# LEDcontroller.net
KiCad netlist of a schematic drawn in Altium Designer
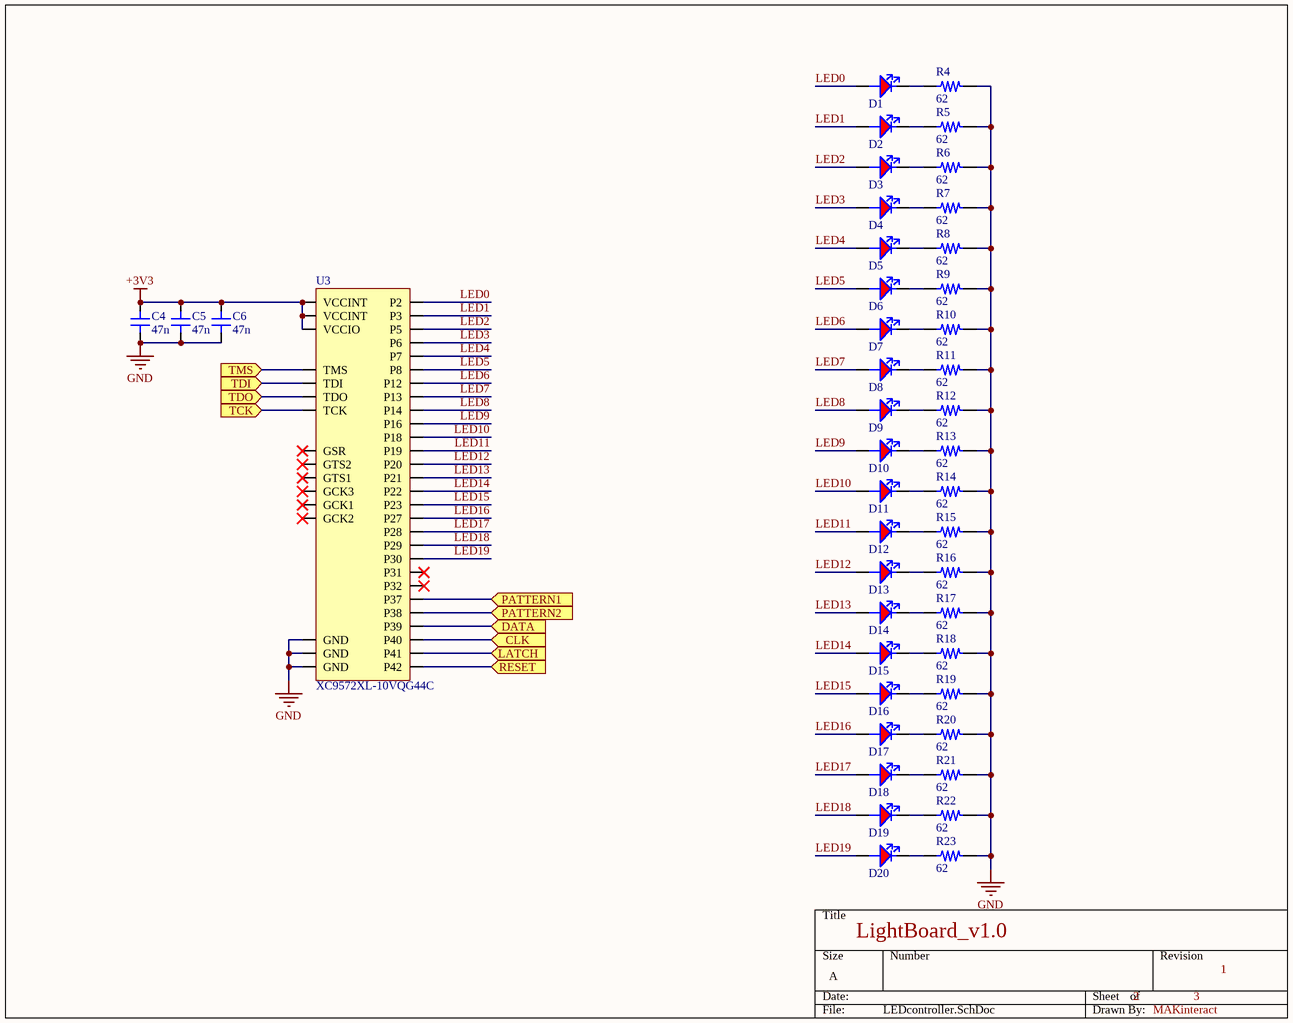
[diagram p0: LEDcontroller.SchDoc]

(export (version "E")
  (design (tool "Eeschema 10.0.6"))
  (components
    (comp (ref "C4")
      (value "47n")
      (description "Cap Ceramic 0.047uF 50V X7R 5% SMD 0805 125C Paper T/R")
      (fields
        (field (name "MANUFACTURER") "Yageo")
        (field (name "MANUFACTURER PART NUMBER") "CC0805JRX7R9BB473")
      )
      (libsource (lib "LightBoard_v1.0") (part "C0805_47n"))
    )
    (comp (ref "C5")
      (value "47n")
      (description "Cap Ceramic 0.047uF 50V X7R 5% SMD 0805 125C Paper T/R")
      (fields
        (field (name "MANUFACTURER") "Yageo")
        (field (name "MANUFACTURER PART NUMBER") "CC0805JRX7R9BB473")
      )
      (libsource (lib "LightBoard_v1.0") (part "C0805_47n"))
    )
    (comp (ref "C6")
      (value "47n")
      (description "Cap Ceramic 0.047uF 50V X7R 5% SMD 0805 125C Paper T/R")
      (fields
        (field (name "MANUFACTURER") "Yageo")
        (field (name "MANUFACTURER PART NUMBER") "CC0805JRX7R9BB473")
      )
      (libsource (lib "LightBoard_v1.0") (part "C0805_47n"))
    )
    (comp (ref "D1")
      (value "LED0402_RED")
      (description "Led red")
      (fields
        (field (name "MANUFACTURER") "Everlight")
        (field (name "MANUFACTURER PART NUMBER") "EAST1005BA0")
      )
      (libsource (lib "LightBoard_v1.0") (part "LED0402_RED"))
    )
    (comp (ref "D2")
      (value "LED0402_RED")
      (description "Led red")
      (fields
        (field (name "MANUFACTURER") "Everlight")
        (field (name "MANUFACTURER PART NUMBER") "EAST1005BA0")
      )
      (libsource (lib "LightBoard_v1.0") (part "LED0402_RED"))
    )
    (comp (ref "D3")
      (value "LED0402_RED")
      (description "Led red")
      (fields
        (field (name "MANUFACTURER") "Everlight")
        (field (name "MANUFACTURER PART NUMBER") "EAST1005BA0")
      )
      (libsource (lib "LightBoard_v1.0") (part "LED0402_RED"))
    )
    (comp (ref "D4")
      (value "LED0402_RED")
      (description "Led red")
      (fields
        (field (name "MANUFACTURER") "Everlight")
        (field (name "MANUFACTURER PART NUMBER") "EAST1005BA0")
      )
      (libsource (lib "LightBoard_v1.0") (part "LED0402_RED"))
    )
    (comp (ref "D5")
      (value "LED0402_RED")
      (description "Led red")
      (fields
        (field (name "MANUFACTURER") "Everlight")
        (field (name "MANUFACTURER PART NUMBER") "EAST1005BA0")
      )
      (libsource (lib "LightBoard_v1.0") (part "LED0402_RED"))
    )
    (comp (ref "D6")
      (value "LED0402_RED")
      (description "Led red")
      (fields
        (field (name "MANUFACTURER") "Everlight")
        (field (name "MANUFACTURER PART NUMBER") "EAST1005BA0")
      )
      (libsource (lib "LightBoard_v1.0") (part "LED0402_RED"))
    )
    (comp (ref "D7")
      (value "LED0402_RED")
      (description "Led red")
      (fields
        (field (name "MANUFACTURER") "Everlight")
        (field (name "MANUFACTURER PART NUMBER") "EAST1005BA0")
      )
      (libsource (lib "LightBoard_v1.0") (part "LED0402_RED"))
    )
    (comp (ref "D8")
      (value "LED0402_RED")
      (description "Led red")
      (fields
        (field (name "MANUFACTURER") "Everlight")
        (field (name "MANUFACTURER PART NUMBER") "EAST1005BA0")
      )
      (libsource (lib "LightBoard_v1.0") (part "LED0402_RED"))
    )
    (comp (ref "D9")
      (value "LED0402_RED")
      (description "Led red")
      (fields
        (field (name "MANUFACTURER") "Everlight")
        (field (name "MANUFACTURER PART NUMBER") "EAST1005BA0")
      )
      (libsource (lib "LightBoard_v1.0") (part "LED0402_RED"))
    )
    (comp (ref "D10")
      (value "LED0402_RED")
      (description "Led red")
      (fields
        (field (name "MANUFACTURER") "Everlight")
        (field (name "MANUFACTURER PART NUMBER") "EAST1005BA0")
      )
      (libsource (lib "LightBoard_v1.0") (part "LED0402_RED"))
    )
    (comp (ref "D11")
      (value "LED0402_RED")
      (description "Led red")
      (fields
        (field (name "MANUFACTURER") "Everlight")
        (field (name "MANUFACTURER PART NUMBER") "EAST1005BA0")
      )
      (libsource (lib "LightBoard_v1.0") (part "LED0402_RED"))
    )
    (comp (ref "D12")
      (value "LED0402_RED")
      (description "Led red")
      (fields
        (field (name "MANUFACTURER") "Everlight")
        (field (name "MANUFACTURER PART NUMBER") "EAST1005BA0")
      )
      (libsource (lib "LightBoard_v1.0") (part "LED0402_RED"))
    )
    (comp (ref "D13")
      (value "LED0402_RED")
      (description "Led red")
      (fields
        (field (name "MANUFACTURER") "Everlight")
        (field (name "MANUFACTURER PART NUMBER") "EAST1005BA0")
      )
      (libsource (lib "LightBoard_v1.0") (part "LED0402_RED"))
    )
    (comp (ref "D14")
      (value "LED0402_RED")
      (description "Led red")
      (fields
        (field (name "MANUFACTURER") "Everlight")
        (field (name "MANUFACTURER PART NUMBER") "EAST1005BA0")
      )
      (libsource (lib "LightBoard_v1.0") (part "LED0402_RED"))
    )
    (comp (ref "D15")
      (value "LED0402_RED")
      (description "Led red")
      (fields
        (field (name "MANUFACTURER") "Everlight")
        (field (name "MANUFACTURER PART NUMBER") "EAST1005BA0")
      )
      (libsource (lib "LightBoard_v1.0") (part "LED0402_RED"))
    )
    (comp (ref "D16")
      (value "LED0402_RED")
      (description "Led red")
      (fields
        (field (name "MANUFACTURER") "Everlight")
        (field (name "MANUFACTURER PART NUMBER") "EAST1005BA0")
      )
      (libsource (lib "LightBoard_v1.0") (part "LED0402_RED"))
    )
    (comp (ref "D17")
      (value "LED0402_RED")
      (description "Led red")
      (fields
        (field (name "MANUFACTURER") "Everlight")
        (field (name "MANUFACTURER PART NUMBER") "EAST1005BA0")
      )
      (libsource (lib "LightBoard_v1.0") (part "LED0402_RED"))
    )
    (comp (ref "D18")
      (value "LED0402_RED")
      (description "Led red")
      (fields
        (field (name "MANUFACTURER") "Everlight")
        (field (name "MANUFACTURER PART NUMBER") "EAST1005BA0")
      )
      (libsource (lib "LightBoard_v1.0") (part "LED0402_RED"))
    )
    (comp (ref "D19")
      (value "LED0402_RED")
      (description "Led red")
      (fields
        (field (name "MANUFACTURER") "Everlight")
        (field (name "MANUFACTURER PART NUMBER") "EAST1005BA0")
      )
      (libsource (lib "LightBoard_v1.0") (part "LED0402_RED"))
    )
    (comp (ref "D20")
      (value "LED0402_RED")
      (description "Led red")
      (fields
        (field (name "MANUFACTURER") "Everlight")
        (field (name "MANUFACTURER PART NUMBER") "EAST1005BA0")
      )
      (libsource (lib "LightBoard_v1.0") (part "LED0402_RED"))
    )
    (comp (ref "R4")
      (value "62")
      (description "RES SMD 62 OHM 1% 1/16W 0402")
      (fields
        (field (name "MANUFACTURER") "Yageo")
        (field (name "MANUFACTURER PART NUMBER") "RC0402FR-0762RL")
      )
      (libsource (lib "LightBoard_v1.0") (part "R0402_62"))
    )
    (comp (ref "R5")
      (value "62")
      (description "RES SMD 62 OHM 1% 1/16W 0402")
      (fields
        (field (name "MANUFACTURER") "Yageo")
        (field (name "MANUFACTURER PART NUMBER") "RC0402FR-0762RL")
      )
      (libsource (lib "LightBoard_v1.0") (part "R0402_62"))
    )
    (comp (ref "R6")
      (value "62")
      (description "RES SMD 62 OHM 1% 1/16W 0402")
      (fields
        (field (name "MANUFACTURER") "Yageo")
        (field (name "MANUFACTURER PART NUMBER") "RC0402FR-0762RL")
      )
      (libsource (lib "LightBoard_v1.0") (part "R0402_62"))
    )
    (comp (ref "R7")
      (value "62")
      (description "RES SMD 62 OHM 1% 1/16W 0402")
      (fields
        (field (name "MANUFACTURER") "Yageo")
        (field (name "MANUFACTURER PART NUMBER") "RC0402FR-0762RL")
      )
      (libsource (lib "LightBoard_v1.0") (part "R0402_62"))
    )
    (comp (ref "R8")
      (value "62")
      (description "RES SMD 62 OHM 1% 1/16W 0402")
      (fields
        (field (name "MANUFACTURER") "Yageo")
        (field (name "MANUFACTURER PART NUMBER") "RC0402FR-0762RL")
      )
      (libsource (lib "LightBoard_v1.0") (part "R0402_62"))
    )
    (comp (ref "R9")
      (value "62")
      (description "RES SMD 62 OHM 1% 1/16W 0402")
      (fields
        (field (name "MANUFACTURER") "Yageo")
        (field (name "MANUFACTURER PART NUMBER") "RC0402FR-0762RL")
      )
      (libsource (lib "LightBoard_v1.0") (part "R0402_62"))
    )
    (comp (ref "R10")
      (value "62")
      (description "RES SMD 62 OHM 1% 1/16W 0402")
      (fields
        (field (name "MANUFACTURER") "Yageo")
        (field (name "MANUFACTURER PART NUMBER") "RC0402FR-0762RL")
      )
      (libsource (lib "LightBoard_v1.0") (part "R0402_62"))
    )
    (comp (ref "R11")
      (value "62")
      (description "RES SMD 62 OHM 1% 1/16W 0402")
      (fields
        (field (name "MANUFACTURER") "Yageo")
        (field (name "MANUFACTURER PART NUMBER") "RC0402FR-0762RL")
      )
      (libsource (lib "LightBoard_v1.0") (part "R0402_62"))
    )
    (comp (ref "R12")
      (value "62")
      (description "RES SMD 62 OHM 1% 1/16W 0402")
      (fields
        (field (name "MANUFACTURER") "Yageo")
        (field (name "MANUFACTURER PART NUMBER") "RC0402FR-0762RL")
      )
      (libsource (lib "LightBoard_v1.0") (part "R0402_62"))
    )
    (comp (ref "R13")
      (value "62")
      (description "RES SMD 62 OHM 1% 1/16W 0402")
      (fields
        (field (name "MANUFACTURER") "Yageo")
        (field (name "MANUFACTURER PART NUMBER") "RC0402FR-0762RL")
      )
      (libsource (lib "LightBoard_v1.0") (part "R0402_62"))
    )
    (comp (ref "R14")
      (value "62")
      (description "RES SMD 62 OHM 1% 1/16W 0402")
      (fields
        (field (name "MANUFACTURER") "Yageo")
        (field (name "MANUFACTURER PART NUMBER") "RC0402FR-0762RL")
      )
      (libsource (lib "LightBoard_v1.0") (part "R0402_62"))
    )
    (comp (ref "R15")
      (value "62")
      (description "RES SMD 62 OHM 1% 1/16W 0402")
      (fields
        (field (name "MANUFACTURER") "Yageo")
        (field (name "MANUFACTURER PART NUMBER") "RC0402FR-0762RL")
      )
      (libsource (lib "LightBoard_v1.0") (part "R0402_62"))
    )
    (comp (ref "R16")
      (value "62")
      (description "RES SMD 62 OHM 1% 1/16W 0402")
      (fields
        (field (name "MANUFACTURER") "Yageo")
        (field (name "MANUFACTURER PART NUMBER") "RC0402FR-0762RL")
      )
      (libsource (lib "LightBoard_v1.0") (part "R0402_62"))
    )
    (comp (ref "R17")
      (value "62")
      (description "RES SMD 62 OHM 1% 1/16W 0402")
      (fields
        (field (name "MANUFACTURER") "Yageo")
        (field (name "MANUFACTURER PART NUMBER") "RC0402FR-0762RL")
      )
      (libsource (lib "LightBoard_v1.0") (part "R0402_62"))
    )
    (comp (ref "R18")
      (value "62")
      (description "RES SMD 62 OHM 1% 1/16W 0402")
      (fields
        (field (name "MANUFACTURER") "Yageo")
        (field (name "MANUFACTURER PART NUMBER") "RC0402FR-0762RL")
      )
      (libsource (lib "LightBoard_v1.0") (part "R0402_62"))
    )
    (comp (ref "R19")
      (value "62")
      (description "RES SMD 62 OHM 1% 1/16W 0402")
      (fields
        (field (name "MANUFACTURER") "Yageo")
        (field (name "MANUFACTURER PART NUMBER") "RC0402FR-0762RL")
      )
      (libsource (lib "LightBoard_v1.0") (part "R0402_62"))
    )
    (comp (ref "R20")
      (value "62")
      (description "RES SMD 62 OHM 1% 1/16W 0402")
      (fields
        (field (name "MANUFACTURER") "Yageo")
        (field (name "MANUFACTURER PART NUMBER") "RC0402FR-0762RL")
      )
      (libsource (lib "LightBoard_v1.0") (part "R0402_62"))
    )
    (comp (ref "R21")
      (value "62")
      (description "RES SMD 62 OHM 1% 1/16W 0402")
      (fields
        (field (name "MANUFACTURER") "Yageo")
        (field (name "MANUFACTURER PART NUMBER") "RC0402FR-0762RL")
      )
      (libsource (lib "LightBoard_v1.0") (part "R0402_62"))
    )
    (comp (ref "R22")
      (value "62")
      (description "RES SMD 62 OHM 1% 1/16W 0402")
      (fields
        (field (name "MANUFACTURER") "Yageo")
        (field (name "MANUFACTURER PART NUMBER") "RC0402FR-0762RL")
      )
      (libsource (lib "LightBoard_v1.0") (part "R0402_62"))
    )
    (comp (ref "R23")
      (value "62")
      (description "RES SMD 62 OHM 1% 1/16W 0402")
      (fields
        (field (name "MANUFACTURER") "Yageo")
        (field (name "MANUFACTURER PART NUMBER") "RC0402FR-0762RL")
      )
      (libsource (lib "LightBoard_v1.0") (part "R0402_62"))
    )
    (comp (ref "U3")
      (value "XC9572XL-10VQG44C")
      (description "XILINX - XC9572XL-10VQG44C. - CPLD, 72 MACROCELL, 3.3V, 44VQFP")
      (fields (field (name "MANUFACTURER") "Xilinx"))
      (libsource (lib "LightBoard_v1.0") (part "XC9572XL"))
    )
  )
  (nets
    (net (code "1") (name "+3V3") (class "Default")
      (node (ref "C4") (pin "2") (pinfunction "2_2") (pintype "passive"))
      (node (ref "C5") (pin "2") (pinfunction "2_2") (pintype "passive"))
      (node (ref "C6") (pin "2") (pinfunction "2_2") (pintype "passive"))
      (node (ref "U3") (pin "15") (pinfunction "VCCINT_15") (pintype "passive"))
      (node (ref "U3") (pin "26") (pinfunction "VCCIO_26") (pintype "passive"))
      (node (ref "U3") (pin "35") (pinfunction "VCCINT_35") (pintype "passive"))
    )
    (net (code "2") (name "/CLK") (class "Default")
      (node (ref "U3") (pin "40") (pinfunction "P40_40") (pintype "passive"))
    )
    (net (code "3") (name "/DATA") (class "Default")
      (node (ref "U3") (pin "39") (pinfunction "P39_39") (pintype "passive"))
    )
    (net (code "4") (name "/LATCH") (class "Default")
      (node (ref "U3") (pin "41") (pinfunction "P41_41") (pintype "passive"))
    )
    (net (code "5") (name "/LED0") (class "Default")
      (node (ref "D1") (pin "1") (pinfunction "A_1") (pintype "passive"))
      (node (ref "U3") (pin "2") (pinfunction "P2_2") (pintype "passive"))
    )
    (net (code "6") (name "/LED1") (class "Default")
      (node (ref "D2") (pin "1") (pinfunction "A_1") (pintype "passive"))
      (node (ref "U3") (pin "3") (pinfunction "P3_3") (pintype "passive"))
    )
    (net (code "7") (name "/LED2") (class "Default")
      (node (ref "D3") (pin "1") (pinfunction "A_1") (pintype "passive"))
      (node (ref "U3") (pin "5") (pinfunction "P5_5") (pintype "passive"))
    )
    (net (code "8") (name "/LED3") (class "Default")
      (node (ref "D4") (pin "1") (pinfunction "A_1") (pintype "passive"))
      (node (ref "U3") (pin "6") (pinfunction "P6_6") (pintype "passive"))
    )
    (net (code "9") (name "/LED4") (class "Default")
      (node (ref "D5") (pin "1") (pinfunction "A_1") (pintype "passive"))
      (node (ref "U3") (pin "7") (pinfunction "P7_7") (pintype "passive"))
    )
    (net (code "10") (name "/LED5") (class "Default")
      (node (ref "D6") (pin "1") (pinfunction "A_1") (pintype "passive"))
      (node (ref "U3") (pin "8") (pinfunction "P8_8") (pintype "passive"))
    )
    (net (code "11") (name "/LED6") (class "Default")
      (node (ref "D7") (pin "1") (pinfunction "A_1") (pintype "passive"))
      (node (ref "U3") (pin "12") (pinfunction "P12_12") (pintype "passive"))
    )
    (net (code "12") (name "/LED7") (class "Default")
      (node (ref "D8") (pin "1") (pinfunction "A_1") (pintype "passive"))
      (node (ref "U3") (pin "13") (pinfunction "P13_13") (pintype "passive"))
    )
    (net (code "13") (name "/LED8") (class "Default")
      (node (ref "D9") (pin "1") (pinfunction "A_1") (pintype "passive"))
      (node (ref "U3") (pin "14") (pinfunction "P14_14") (pintype "passive"))
    )
    (net (code "14") (name "/LED9") (class "Default")
      (node (ref "D10") (pin "1") (pinfunction "A_1") (pintype "passive"))
      (node (ref "U3") (pin "16") (pinfunction "P16_16") (pintype "passive"))
    )
    (net (code "15") (name "/LED10") (class "Default")
      (node (ref "D11") (pin "1") (pinfunction "A_1") (pintype "passive"))
      (node (ref "U3") (pin "18") (pinfunction "P18_18") (pintype "passive"))
    )
    (net (code "16") (name "/LED11") (class "Default")
      (node (ref "D12") (pin "1") (pinfunction "A_1") (pintype "passive"))
      (node (ref "U3") (pin "19") (pinfunction "P19_19") (pintype "passive"))
    )
    (net (code "17") (name "/LED12") (class "Default")
      (node (ref "D13") (pin "1") (pinfunction "A_1") (pintype "passive"))
      (node (ref "U3") (pin "20") (pinfunction "P20_20") (pintype "passive"))
    )
    (net (code "18") (name "/LED13") (class "Default")
      (node (ref "D14") (pin "1") (pinfunction "A_1") (pintype "passive"))
      (node (ref "U3") (pin "21") (pinfunction "P21_21") (pintype "passive"))
    )
    (net (code "19") (name "/LED14") (class "Default")
      (node (ref "D15") (pin "1") (pinfunction "A_1") (pintype "passive"))
      (node (ref "U3") (pin "22") (pinfunction "P22_22") (pintype "passive"))
    )
    (net (code "20") (name "/LED15") (class "Default")
      (node (ref "D16") (pin "1") (pinfunction "A_1") (pintype "passive"))
      (node (ref "U3") (pin "23") (pinfunction "P23_23") (pintype "passive"))
    )
    (net (code "21") (name "/LED16") (class "Default")
      (node (ref "D17") (pin "1") (pinfunction "A_1") (pintype "passive"))
      (node (ref "U3") (pin "27") (pinfunction "P27_27") (pintype "passive"))
    )
    (net (code "22") (name "/LED17") (class "Default")
      (node (ref "D18") (pin "1") (pinfunction "A_1") (pintype "passive"))
      (node (ref "U3") (pin "28") (pinfunction "P28_28") (pintype "passive"))
    )
    (net (code "23") (name "/LED18") (class "Default")
      (node (ref "D19") (pin "1") (pinfunction "A_1") (pintype "passive"))
      (node (ref "U3") (pin "29") (pinfunction "P29_29") (pintype "passive"))
    )
    (net (code "24") (name "/LED19") (class "Default")
      (node (ref "D20") (pin "1") (pinfunction "A_1") (pintype "passive"))
      (node (ref "U3") (pin "30") (pinfunction "P30_30") (pintype "passive"))
    )
    (net (code "25") (name "/PATTERN1") (class "Default")
      (node (ref "U3") (pin "37") (pinfunction "P37_37") (pintype "passive"))
    )
    (net (code "26") (name "/PATTERN2") (class "Default")
      (node (ref "U3") (pin "38") (pinfunction "P38_38") (pintype "passive"))
    )
    (net (code "27") (name "/RESET") (class "Default")
      (node (ref "U3") (pin "42") (pinfunction "P42_42") (pintype "passive"))
    )
    (net (code "28") (name "/TCK") (class "Default")
      (node (ref "U3") (pin "11") (pinfunction "TCK_11") (pintype "passive"))
    )
    (net (code "29") (name "/TDI") (class "Default")
      (node (ref "U3") (pin "9") (pinfunction "TDI_9") (pintype "passive"))
    )
    (net (code "30") (name "/TDO") (class "Default")
      (node (ref "U3") (pin "24") (pinfunction "TDO_24") (pintype "passive"))
    )
    (net (code "31") (name "/TMS") (class "Default")
      (node (ref "U3") (pin "10") (pinfunction "TMS_10") (pintype "passive"))
    )
    (net (code "32") (name "GND") (class "Default")
      (node (ref "C4") (pin "1") (pinfunction "1_1") (pintype "passive"))
      (node (ref "C5") (pin "1") (pinfunction "1_1") (pintype "passive"))
      (node (ref "C6") (pin "1") (pinfunction "1_1") (pintype "passive"))
      (node (ref "R10") (pin "2") (pinfunction "2_2") (pintype "passive"))
      (node (ref "R11") (pin "2") (pinfunction "2_2") (pintype "passive"))
      (node (ref "R12") (pin "2") (pinfunction "2_2") (pintype "passive"))
      (node (ref "R13") (pin "2") (pinfunction "2_2") (pintype "passive"))
      (node (ref "R14") (pin "2") (pinfunction "2_2") (pintype "passive"))
      (node (ref "R15") (pin "2") (pinfunction "2_2") (pintype "passive"))
      (node (ref "R16") (pin "2") (pinfunction "2_2") (pintype "passive"))
      (node (ref "R17") (pin "2") (pinfunction "2_2") (pintype "passive"))
      (node (ref "R18") (pin "2") (pinfunction "2_2") (pintype "passive"))
      (node (ref "R19") (pin "2") (pinfunction "2_2") (pintype "passive"))
      (node (ref "R20") (pin "2") (pinfunction "2_2") (pintype "passive"))
      (node (ref "R21") (pin "2") (pinfunction "2_2") (pintype "passive"))
      (node (ref "R22") (pin "2") (pinfunction "2_2") (pintype "passive"))
      (node (ref "R23") (pin "2") (pinfunction "2_2") (pintype "passive"))
      (node (ref "R4") (pin "2") (pinfunction "2_2") (pintype "passive"))
      (node (ref "R5") (pin "2") (pinfunction "2_2") (pintype "passive"))
      (node (ref "R6") (pin "2") (pinfunction "2_2") (pintype "passive"))
      (node (ref "R7") (pin "2") (pinfunction "2_2") (pintype "passive"))
      (node (ref "R8") (pin "2") (pinfunction "2_2") (pintype "passive"))
      (node (ref "R9") (pin "2") (pinfunction "2_2") (pintype "passive"))
      (node (ref "U3") (pin "17") (pinfunction "GND_17") (pintype "passive"))
      (node (ref "U3") (pin "25") (pinfunction "GND_25") (pintype "passive"))
      (node (ref "U3") (pin "4") (pinfunction "GND_4") (pintype "passive"))
    )
    (net (code "33") (name "Net-(D1-K)") (class "Default")
      (node (ref "D1") (pin "2") (pinfunction "K_2") (pintype "passive"))
      (node (ref "R4") (pin "1") (pinfunction "1_1") (pintype "passive"))
    )
    (net (code "34") (name "Net-(D2-K)") (class "Default")
      (node (ref "D2") (pin "2") (pinfunction "K_2") (pintype "passive"))
      (node (ref "R5") (pin "1") (pinfunction "1_1") (pintype "passive"))
    )
    (net (code "35") (name "Net-(D3-K)") (class "Default")
      (node (ref "D3") (pin "2") (pinfunction "K_2") (pintype "passive"))
      (node (ref "R6") (pin "1") (pinfunction "1_1") (pintype "passive"))
    )
    (net (code "36") (name "Net-(D4-K)") (class "Default")
      (node (ref "D4") (pin "2") (pinfunction "K_2") (pintype "passive"))
      (node (ref "R7") (pin "1") (pinfunction "1_1") (pintype "passive"))
    )
    (net (code "37") (name "Net-(D5-K)") (class "Default")
      (node (ref "D5") (pin "2") (pinfunction "K_2") (pintype "passive"))
      (node (ref "R8") (pin "1") (pinfunction "1_1") (pintype "passive"))
    )
    (net (code "38") (name "Net-(D6-K)") (class "Default")
      (node (ref "D6") (pin "2") (pinfunction "K_2") (pintype "passive"))
      (node (ref "R9") (pin "1") (pinfunction "1_1") (pintype "passive"))
    )
    (net (code "39") (name "Net-(D7-K)") (class "Default")
      (node (ref "D7") (pin "2") (pinfunction "K_2") (pintype "passive"))
      (node (ref "R10") (pin "1") (pinfunction "1_1") (pintype "passive"))
    )
    (net (code "40") (name "Net-(D8-K)") (class "Default")
      (node (ref "D8") (pin "2") (pinfunction "K_2") (pintype "passive"))
      (node (ref "R11") (pin "1") (pinfunction "1_1") (pintype "passive"))
    )
    (net (code "41") (name "Net-(D9-K)") (class "Default")
      (node (ref "D9") (pin "2") (pinfunction "K_2") (pintype "passive"))
      (node (ref "R12") (pin "1") (pinfunction "1_1") (pintype "passive"))
    )
    (net (code "42") (name "Net-(D10-K)") (class "Default")
      (node (ref "D10") (pin "2") (pinfunction "K_2") (pintype "passive"))
      (node (ref "R13") (pin "1") (pinfunction "1_1") (pintype "passive"))
    )
    (net (code "43") (name "Net-(D11-K)") (class "Default")
      (node (ref "D11") (pin "2") (pinfunction "K_2") (pintype "passive"))
      (node (ref "R14") (pin "1") (pinfunction "1_1") (pintype "passive"))
    )
    (net (code "44") (name "Net-(D12-K)") (class "Default")
      (node (ref "D12") (pin "2") (pinfunction "K_2") (pintype "passive"))
      (node (ref "R15") (pin "1") (pinfunction "1_1") (pintype "passive"))
    )
    (net (code "45") (name "Net-(D13-K)") (class "Default")
      (node (ref "D13") (pin "2") (pinfunction "K_2") (pintype "passive"))
      (node (ref "R16") (pin "1") (pinfunction "1_1") (pintype "passive"))
    )
    (net (code "46") (name "Net-(D14-K)") (class "Default")
      (node (ref "D14") (pin "2") (pinfunction "K_2") (pintype "passive"))
      (node (ref "R17") (pin "1") (pinfunction "1_1") (pintype "passive"))
    )
    (net (code "47") (name "Net-(D15-K)") (class "Default")
      (node (ref "D15") (pin "2") (pinfunction "K_2") (pintype "passive"))
      (node (ref "R18") (pin "1") (pinfunction "1_1") (pintype "passive"))
    )
    (net (code "48") (name "Net-(D16-K)") (class "Default")
      (node (ref "D16") (pin "2") (pinfunction "K_2") (pintype "passive"))
      (node (ref "R19") (pin "1") (pinfunction "1_1") (pintype "passive"))
    )
    (net (code "49") (name "Net-(D17-K)") (class "Default")
      (node (ref "D17") (pin "2") (pinfunction "K_2") (pintype "passive"))
      (node (ref "R20") (pin "1") (pinfunction "1_1") (pintype "passive"))
    )
    (net (code "50") (name "Net-(D18-K)") (class "Default")
      (node (ref "D18") (pin "2") (pinfunction "K_2") (pintype "passive"))
      (node (ref "R21") (pin "1") (pinfunction "1_1") (pintype "passive"))
    )
    (net (code "51") (name "Net-(D19-K)") (class "Default")
      (node (ref "D19") (pin "2") (pinfunction "K_2") (pintype "passive"))
      (node (ref "R22") (pin "1") (pinfunction "1_1") (pintype "passive"))
    )
    (net (code "52") (name "Net-(D20-K)") (class "Default")
      (node (ref "D20") (pin "2") (pinfunction "K_2") (pintype "passive"))
      (node (ref "R23") (pin "1") (pinfunction "1_1") (pintype "passive"))
    )
    (net (code "53") (name "unconnected-(U3-GCK1-Pad43)") (class "Default")
      (node (ref "U3") (pin "43") (pinfunction "GCK1_43") (pintype "passive+no_connect"))
    )
    (net (code "54") (name "unconnected-(U3-GCK2-Pad44)") (class "Default")
      (node (ref "U3") (pin "44") (pinfunction "GCK2_44") (pintype "passive+no_connect"))
    )
    (net (code "55") (name "unconnected-(U3-GCK3-Pad1)") (class "Default")
      (node (ref "U3") (pin "1") (pinfunction "GCK3_1") (pintype "passive+no_connect"))
    )
    (net (code "56") (name "unconnected-(U3-GSR-Pad33)") (class "Default")
      (node (ref "U3") (pin "33") (pinfunction "GSR_33") (pintype "passive+no_connect"))
    )
    (net (code "57") (name "unconnected-(U3-GTS1-Pad36)") (class "Default")
      (node (ref "U3") (pin "36") (pinfunction "GTS1_36") (pintype "passive+no_connect"))
    )
    (net (code "58") (name "unconnected-(U3-GTS2-Pad34)") (class "Default")
      (node (ref "U3") (pin "34") (pinfunction "GTS2_34") (pintype "passive+no_connect"))
    )
    (net (code "59") (name "unconnected-(U3-P31-Pad31)") (class "Default")
      (node (ref "U3") (pin "31") (pinfunction "P31_31") (pintype "passive+no_connect"))
    )
    (net (code "60") (name "unconnected-(U3-P32-Pad32)") (class "Default")
      (node (ref "U3") (pin "32") (pinfunction "P32_32") (pintype "passive+no_connect"))
    )
  )
)
